# Power_Supply_AC_to_DC.net
KiCad netlist of a schematic drawn in Altium Designer
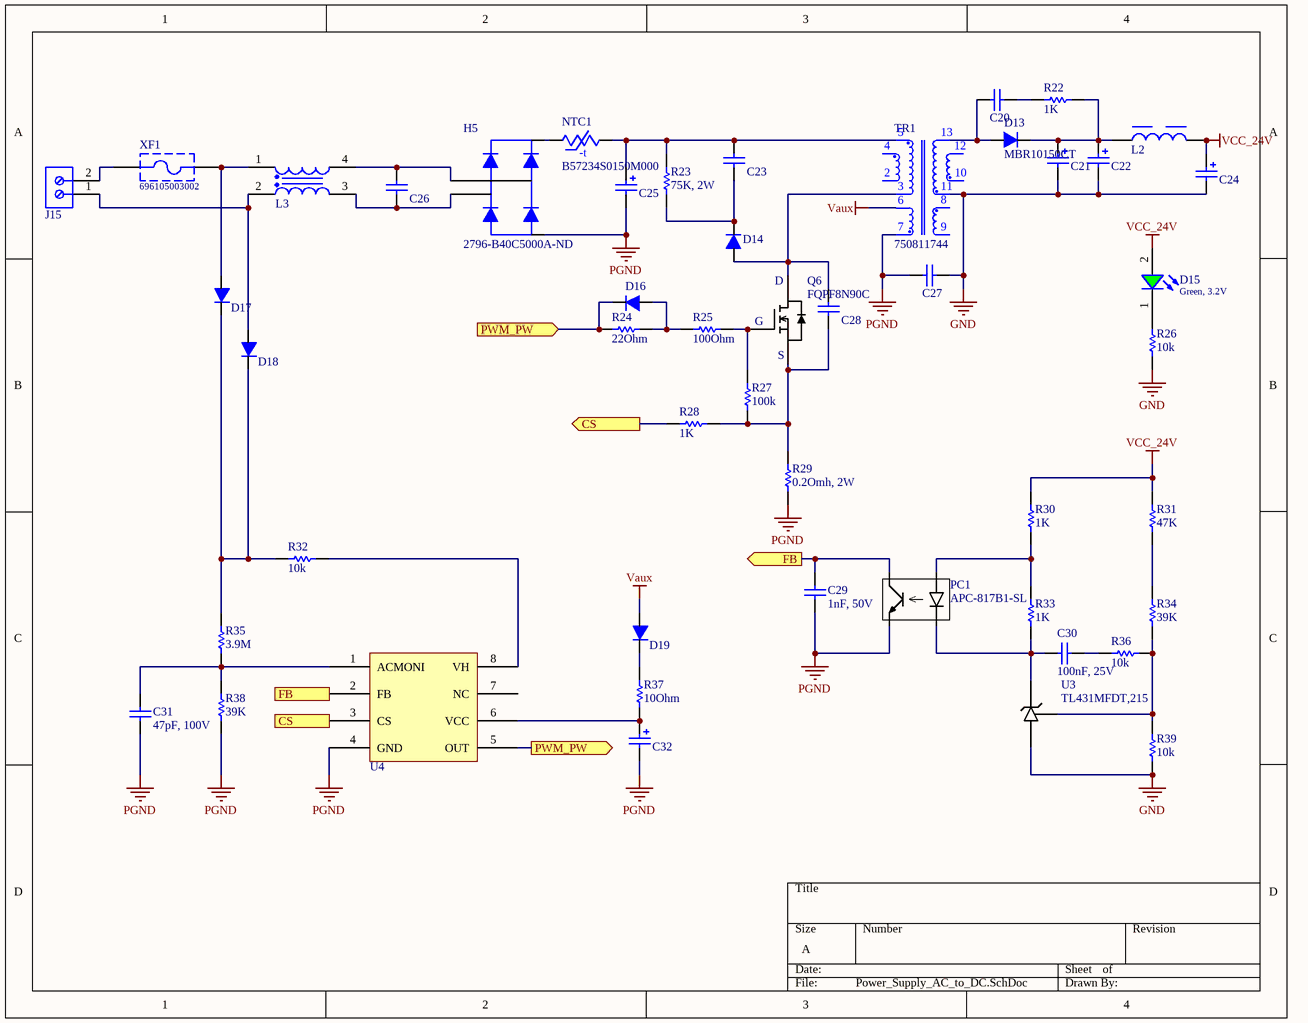
[diagram p0: Power_Supply_AC_to_DC.SchDoc]

(export (version "E")
  (design (tool "Eeschema 10.0.6"))
  (components
    (comp (ref "C20")
      (value "1nF")
      (footprint "WCAP-CSMH_0805_L2W1.25H0.8_Reflow")
      (fields
        (field (name "MANUFACTURER PART NUMBER") "885342207013")
        (field (name "MANUFACTURER") "Wurth Elektronik")
      )
      (libsource (lib "Altium_WCAP-CSMH (rev22c)") (part "885342207013"))
    )
    (comp (ref "C21")
      (value "1200uF")
      (footprint "WCAP-ATG8_D16H31.5")
      (description "WCAP-ATG8 Aluminum Electrolytic Capacitor, Radial THT, D16xH31.5mm, 1200uF, 63V")
      (fields
        (field (name "MANUFACTURER") "Wurth Elektronik")
        (field (name "MANUFACTURER PART NUMBER") "860010780025")
      )
      (libsource (lib "Altium_WCAP-ATG8 (rev22a)") (part "860010780025"))
    )
    (comp (ref "C22")
      (value "1200uF")
      (footprint "WCAP-ATG8_D16H31.5")
      (description "WCAP-ATG8 Aluminum Electrolytic Capacitor, Radial THT, D16xH31.5mm, 1200uF, 63V")
      (fields
        (field (name "MANUFACTURER") "Wurth Elektronik")
        (field (name "MANUFACTURER PART NUMBER") "860010780025")
      )
      (libsource (lib "Altium_WCAP-ATG8 (rev22a)") (part "860010780025"))
    )
    (comp (ref "C23")
      (value "4.7nF")
      (footprint "WCAP-CSMH_1206_L3.2W1.6H1.25")
      (fields
        (field (name "MANUFACTURER PART NUMBER") "885342208008")
        (field (name "MANUFACTURER") "Wurth Elektronik")
      )
      (libsource (lib "Altium_WCAP-CSMH (rev22c)") (part "885342208008"))
    )
    (comp (ref "C24")
      (value "100uF")
      (footprint "WCAP-ATG8_D8H11.5")
      (description "WCAP-ATG8 Aluminum Electrolytic Capacitor, Radial THT, D8xH11.5mm, 100uF, 50V")
      (fields
        (field (name "MANUFACTURER") "Wurth Elektronik")
        (field (name "MANUFACTURER PART NUMBER") "860010674014")
      )
      (libsource (lib "Altium_WCAP-ATG8 (rev22a)") (part "860010674014"))
    )
    (comp (ref "C25")
      (value "220uF")
      (footprint "WCAP-AI3H_D22H50")
      (description "WCAP-AI3H Aluminum Electrolytic Capacitor, Snap-In, D22xH50mm, 220uF, 450V")
      (fields
        (field (name "MANUFACTURER") "Wurth Elektronik")
        (field (name "MANUFACTURER PART NUMBER") "861141483007")
      )
      (libsource (lib "Altium_WCAP-AI3H (rev22a)") (part "861141483007"))
    )
    (comp (ref "C26")
      (value "2.2uF")
      (footprint "WCAP-FTX2_L26W15H25")
      (description "WCAP-FTX2 Film Capacitor, THT, L26W15H25mm, 2.2uF, 275VAC")
      (fields
        (field (name "MANUFACTURER") "Wurth Elektronik")
        (field (name "MANUFACTURER PART NUMBER") "890324026034")
      )
      (libsource (lib "Altium_WCAP-FTX2 (rev22a)") (part "890324026034"))
    )
    (comp (ref "C27")
      (value "2.2nF")
      (footprint "WCAP-CSSA_2211_L5.7W2.8H2.5")
      (description "WCAP-CSSA Multilayer Ceramic Chip Safety Capacitor, 2211, X7R Class II, X1/Y2, 2.2nF, 250VAC")
      (fields
        (field (name "MANUFACTURER") "Wurth Elektronik")
        (field (name "MANUFACTURER PART NUMBER") "8853522130151")
      )
      (libsource (lib "Altium_WCAP-CSSA (rev22a)") (part "8853522130151"))
    )
    (comp (ref "C28")
      (value "22pF")
      (footprint "WCAP-CSMH_1210_L3.2W2.5H0.95")
      (fields
        (field (name "MANUFACTURER PART NUMBER") "885342009002")
        (field (name "MANUFACTURER") "Wurth Elektronik")
      )
      (libsource (lib "Altium_WCAP-CSMH (rev22c)") (part "885342009002"))
    )
    (comp (ref "C29")
      (value "1nF, 50V")
      (footprint "WCAP-CSGP_0805_H=0.8mm_Reflow")
      (description "WCAP-CSGP Multilayer Ceramic Chip Capacitor, General Purpose, size 0805, NP0, 1nF, 50V")
      (fields
        (field (name "MANUFACTURER PART NUMBER") "885012007063")
        (field (name "MANUFACTURER") "Wurth Elektronik")
      )
      (libsource (lib "Altium_WCAP-CSGP (rev20a)") (part "885012007063"))
    )
    (comp (ref "C30")
      (value "100nF, 25V")
      (footprint "WCAP-CSGP_0805_H=0.8mm_Reflow")
      (description "WCAP-CSGP Multilayer Ceramic Chip Capacitor, General Purpose, size 0805, X7R, 100nF, 25V")
      (fields
        (field (name "MANUFACTURER PART NUMBER") "885012207072")
        (field (name "MANUFACTURER") "Wurth Elektronik")
      )
      (libsource (lib "Altium_WCAP-CSGP (rev20a)") (part "885012207072"))
    )
    (comp (ref "C31")
      (value "47pF, 100V")
      (footprint "WCAP-CSGP_0805_H=0.6mm_Reflow")
      (description "WCAP-CSGP Multilayer Ceramic Chip Capacitor, General Purpose, size 0805, NP0, 47pF, 100V")
      (fields
        (field (name "MANUFACTURER PART NUMBER") "885012007080")
        (field (name "MANUFACTURER") "Wurth Elektronik")
      )
      (libsource (lib "Altium_WCAP-CSGP (rev20a)") (part "885012007080"))
    )
    (comp (ref "C32")
      (value "10uF")
      (footprint "WCAP-ATG8_D5H11")
      (description "WCAP-ATG8 Aluminum Electrolytic Capacitor, Radial THT, D5xH11mm, 10uF, 50V")
      (fields
        (field (name "MANUFACTURER") "Wurth Elektronik")
        (field (name "MANUFACTURER PART NUMBER") "860010672009")
      )
      (libsource (lib "Altium_WCAP-ATG8 (rev22a)") (part "860010672009"))
    )
    (comp (ref "D13")
      (value "MBR10150CT")
      (footprint "MBR10150CT")
      (description "DIODE ARRAY SCHOTTKY 150V TO220")
      (fields (field (name "MFR") "SMC Diode Solutions"))
      (libsource (lib "YenDoo") (part "Diode"))
    )
    (comp (ref "D14")
      (value "RS1M-13-F")
      (footprint "SMA")
      (description "DIODE GEN PURP 1KV 1A SMA")
      (fields (field (name "MFR") "Diodes Incorporated"))
      (libsource (lib "YenDoo") (part "Diode"))
    )
    (comp (ref "D15")
      (value "Green, 3.2V")
      (footprint "WL-SMCW_0603_H=0.7mm")
      (description "WL-SMCW SMT Mono-color Chip LED Waterclear, size 0603, Green, 3.2V, 140deg")
      (fields (field (name "PART NUMBER") "150060GS75000") (field (name "PUBLISHER") "Wurth Elektronik"))
      (libsource (lib "Altium_WL-SMCW (rev20a)") (part "150060GS75000"))
    )
    (comp (ref "D16")
      (value "CDBA360-HF")
      (footprint "SMA")
      (description "DIODE SCHOTTKY 60V 3A DO214AC")
      (fields (field (name "MFR") "Comchip Technology"))
      (libsource (lib "YenDoo") (part "Diode"))
    )
    (comp (ref "D17")
      (value "RFU02VSM8STR")
      (footprint "Flat Lead")
      (description "DIODE GP 800V 200MA TUMD2SM")
      (fields (field (name "MFR") "Rohm Semiconductor"))
      (libsource (lib "YenDoo") (part "Diode"))
    )
    (comp (ref "D18")
      (value "RFU02VSM8STR")
      (footprint "Flat Lead")
      (description "DIODE GP 800V 200MA TUMD2SM")
      (fields (field (name "MFR") "Rohm Semiconductor"))
      (libsource (lib "YenDoo") (part "Diode"))
    )
    (comp (ref "D19")
      (value "RS1M-13-F")
      (footprint "SMA")
      (description "DIODE GEN PURP 1KV 1A SMA")
      (fields (field (name "MFR") "Diodes Incorporated"))
      (libsource (lib "YenDoo") (part "Diode"))
    )
    (comp (ref "H5")
      (value "2796-B40C5000A-ND")
      (footprint "GBJ-4")
      (description "Bridge Rectifier Single Phase Standard 80 V Through Hole 4-SIP")
      (libsource (lib "YenDoo") (part "H Bridge"))
    )
    (comp (ref "J15")
      (value "691137710002")
      (footprint "691137710002")
      (description "WR-TBL Series 1377 Horizontal Entry, Through Hole, pitch 5mm, 2p")
      (fields (field (name "MANUFACTURER") "Wurth Elektronik"))
      (libsource (lib "Altium_WR-TBL (rev22a)") (part "691137710002"))
    )
    (comp (ref "L2")
      (value "10µH, 7A")
      (footprint "WE-LHMI_1040")
      (description "WE-LHMI SMT Power Inductor, size 1040, 10µH, 7A, 30mΩ")
      (fields
        (field (name "MANUFACTURER PART NUMBER") "74437368100")
        (field (name "MANUFACTURER") "Wurth Elektronik")
      )
      (libsource (lib "WE-LHMI (rev22a)") (part "74437368100"))
    )
    (comp (ref "L3")
      (value "13mH")
      (footprint "WE-FC_UT20V")
      (description "WE-FC THT Common Mode Power Line Choke, UT20V, 13mH, 0.8A, 0.708Ω")
      (fields
        (field (name "MANUFACTURER PART NUMBER") "7448640415")
        (field (name "MANUFACTURER") "Wurth Elektronik")
      )
      (libsource (lib "WE-FC (rev22a)") (part "7448640415"))
    )
    (comp (ref "NTC1")
      (value "B57234S0150M000")
      (footprint "NTC")
      (description "THERMISTOR NTC 15OHM 3000K")
      (fields (field (name "MFR") "EPCOS - TDK Electronics") (field (name "TOLERANCE") "±20%"))
      (libsource (lib "YenDoo") (part "NTC"))
    )
    (comp (ref "PC1")
      (value "APC-817B1-SL")
      (footprint "APC-817B1-SL")
      (description "DIP4, DC INPUT, PHOTO TRANSISTOR")
      (fields (field (name "MFR") "American Bright Optoelectronics Corporation"))
      (libsource (lib "YenDoo") (part "Opto Isolator"))
    )
    (comp (ref "Q6")
      (value "FQPF8N90C")
      (footprint "FQPF8N90C")
      (description "MOSFET N-CH 900V 6.3A TO220F")
      (fields (field (name "MFR") "onsemi"))
      (libsource (lib "YenDoo") (part "Mosfet"))
    )
    (comp (ref "R22")
      (value "1K")
      (footprint "RES-SM-2512")
      (description "RES 10 OHM 0.5% 1W 2512")
      (fields (field (name "MFR") "KOA Speer Electronics, Inc.") (field (name "TOLERANCE") "±0.5%"))
      (libsource (lib "PIF_Library") (part "RESISTOR SMD"))
    )
    (comp (ref "R23")
      (value "75K, 2W")
      (footprint "RES-SM-2512")
      (description "RES SMD 75K OHM 1% 2W 2512")
      (fields (field (name "MFR") "TE Connectivity Passive Product") (field (name "TOLERANCE") "±1%"))
      (libsource (lib "PIF_Library") (part "RESISTOR SMD"))
    )
    (comp (ref "R24")
      (value "22Ohm")
      (footprint "RES-SM-0805")
      (description "RES 22 OHM 1% 1/4W 0805")
      (fields (field (name "MFR") "KOA Speer Electronics, Inc.") (field (name "TOLERANCE") "±1%"))
      (libsource (lib "PIF_Library") (part "RESISTOR SMD"))
    )
    (comp (ref "R25")
      (value "100Ohm")
      (footprint "RES-SM-0805")
      (description "RES 100 OHM 5% 1/4W 0805")
      (fields (field (name "MFR") "KOA Speer Electronics, Inc.") (field (name "TOLERANCE") "±5%"))
      (libsource (lib "PIF_Library") (part "RESISTOR SMD"))
    )
    (comp (ref "R26")
      (value "10k")
      (footprint "RES-SM-0805")
      (description "RES 10K OHM 1% 1/4W 0805")
      (fields (field (name "MFR") "KOA Speer Electronics, Inc.") (field (name "TOLERANCE") "±1%"))
      (libsource (lib "PIF_Library") (part "RESISTOR SMD"))
    )
    (comp (ref "R27")
      (value "100k")
      (footprint "RES-SM-0805")
      (description "RES 100K OHM 1% 1/4W 0805")
      (fields (field (name "MFR") "KOA Speer Electronics, Inc.") (field (name "TOLERANCE") "±1%"))
      (libsource (lib "PIF_Library") (part "RESISTOR SMD"))
    )
    (comp (ref "R28")
      (value "1K")
      (footprint "RES-SM-0805")
      (description "RES 1K OHM 5% 1/4W 0805")
      (fields (field (name "MFR") "KOA Speer Electronics, Inc.") (field (name "TOLERANCE") "±5%"))
      (libsource (lib "PIF_Library") (part "RESISTOR SMD"))
    )
    (comp (ref "R29")
      (value "0.2Omh, 2W")
      (footprint "RES-SM-2010")
      (description "RES 0.2 OHM 2.0 W 1% 2010 SMD")
      (fields (field (name "MFR") "Vishay Dale") (field (name "TOLERANCE") "±1%"))
      (libsource (lib "PIF_Library") (part "RESISTOR SMD"))
    )
    (comp (ref "R30")
      (value "1K")
      (footprint "RES-SM-0805")
      (description "RES 1K OHM 5% 1/4W 0805")
      (fields (field (name "MFR") "KOA Speer Electronics, Inc.") (field (name "TOLERANCE") "±5%"))
      (libsource (lib "PIF_Library") (part "RESISTOR SMD"))
    )
    (comp (ref "R31")
      (value "47K")
      (footprint "RES-SM-0805")
      (description "RES 47K OHM 5% 1/4W 0805")
      (fields (field (name "MFR") "KOA Speer Electronics, Inc.") (field (name "TOLERANCE") "±5%"))
      (libsource (lib "PIF_Library") (part "RESISTOR SMD"))
    )
    (comp (ref "R32")
      (value "10k")
      (footprint "RES-SM-0805")
      (description "RES 10K OHM 1% 1/4W 0805")
      (fields (field (name "MFR") "KOA Speer Electronics, Inc.") (field (name "TOLERANCE") "±1%"))
      (libsource (lib "PIF_Library") (part "RESISTOR SMD"))
    )
    (comp (ref "R33")
      (value "1K")
      (footprint "RES-SM-0805")
      (description "RES 1K OHM 5% 1/4W 0805")
      (fields (field (name "MFR") "KOA Speer Electronics, Inc.") (field (name "TOLERANCE") "±5%"))
      (libsource (lib "PIF_Library") (part "RESISTOR SMD"))
    )
    (comp (ref "R34")
      (value "39K")
      (footprint "RES-SM-0805")
      (description "RES 39K OHM 5% 1/4W 0805")
      (fields (field (name "MFR") "KOA Speer Electronics, Inc.") (field (name "TOLERANCE") "±5%"))
      (libsource (lib "PIF_Library") (part "RESISTOR SMD"))
    )
    (comp (ref "R35")
      (value "3.9M")
      (footprint "RES-SM-0805")
      (description "RES 3.9M OHM 5% 1/4W 0805")
      (fields (field (name "MFR") "KOA Speer Electronics, Inc.") (field (name "TOLERANCE") "±5%"))
      (libsource (lib "PIF_Library") (part "RESISTOR SMD"))
    )
    (comp (ref "R36")
      (value "10k")
      (footprint "RES-SM-0805")
      (description "RES 10K OHM 1% 1/4W 0805")
      (fields (field (name "MFR") "KOA Speer Electronics, Inc.") (field (name "TOLERANCE") "±1%"))
      (libsource (lib "PIF_Library") (part "RESISTOR SMD"))
    )
    (comp (ref "R37")
      (value "10Ohm")
      (footprint "RES-SM-0805")
      (description "RES 10 OHM 1% 1/4W 0805")
      (fields (field (name "MFR") "KOA Speer Electronics, Inc.") (field (name "TOLERANCE") "±1%"))
      (libsource (lib "PIF_Library") (part "RESISTOR SMD"))
    )
    (comp (ref "R38")
      (value "39K")
      (footprint "RES-SM-0805")
      (description "RES 39K OHM 5% 1/4W 0805")
      (fields (field (name "MFR") "KOA Speer Electronics, Inc.") (field (name "TOLERANCE") "±5%"))
      (libsource (lib "PIF_Library") (part "RESISTOR SMD"))
    )
    (comp (ref "R39")
      (value "10k")
      (footprint "RES-SM-0805")
      (description "RES 10K OHM 1% 1/4W 0805")
      (fields (field (name "MFR") "KOA Speer Electronics, Inc.") (field (name "TOLERANCE") "±1%"))
      (libsource (lib "PIF_Library") (part "RESISTOR SMD"))
    )
    (comp (ref "TR1")
      (value "750811744")
      (footprint "750811744")
      (description "Flyback Converters For For DC/DC Converters SMPS Transformer 4000Vrms Isolation 80kHz Through Hole")
      (fields (field (name "MFR") "Würth Elektronik"))
      (libsource (lib "YenDoo") (part "750811744"))
    )
    (comp (ref "U3")
      (value "TL431MFDT,215")
      (footprint "TO-236AB")
      (description "IC VREF SHUNT ADJ 2% TO236AB")
      (fields (field (name "MFR") "Nexperia USA Inc.") (field (name "TOLERANCE") "±2%"))
      (libsource (lib "YenDoo") (part "IC Shunt"))
    )
    (comp (ref "U4")
      (value "BM1P061FJ-E2")
      (footprint "SOP-J8")
      (description "IC OFFLINE SWITCH FLYBACK 8SOPJ")
      (fields (field (name "MFR") "Rohm Semiconductor"))
      (libsource (lib "YenDoo") (part "IC PWM"))
    )
    (comp (ref "XF1")
      (value "696105003002")
      (footprint "696105003002")
      (description "WR-FSH Fuseholder THT Blocks PCB Clip Cover")
      (fields (field (name "MANUFACTURER") "Wurth Elektronik"))
      (libsource (lib "Altium_WR-FSH (rev21a)") (part "696105003002"))
    )
  )
  (nets
    (net (code "1") (name "/CS") (class "Default")
      (node (ref "R28") (pin "2") (pinfunction "2_2") (pintype "passive"))
      (node (ref "U4") (pin "3") (pinfunction "CS_3") (pintype "passive"))
    )
    (net (code "2") (name "/FB") (class "Default")
      (node (ref "C29") (pin "2") (pinfunction "2_2") (pintype "passive"))
      (node (ref "PC1") (pin "4") (pinfunction "4_4") (pintype "passive"))
      (node (ref "U4") (pin "2") (pinfunction "FB_2") (pintype "passive"))
    )
    (net (code "3") (name "/PWM_PW") (class "Default")
      (node (ref "D16") (pin "2") (pinfunction "K_2") (pintype "passive"))
      (node (ref "R24") (pin "1") (pinfunction "1_1") (pintype "passive"))
      (node (ref "U4") (pin "5") (pinfunction "OUT_5") (pintype "passive"))
    )
    (net (code "4") (name "GND") (class "Default")
      (node (ref "C21") (pin "2") (pinfunction "N_2") (pintype "passive"))
      (node (ref "C22") (pin "2") (pinfunction "N_2") (pintype "passive"))
      (node (ref "C24") (pin "2") (pinfunction "N_2") (pintype "passive"))
      (node (ref "C27") (pin "1") (pinfunction "1_1") (pintype "passive"))
      (node (ref "R26") (pin "2") (pinfunction "2_2") (pintype "passive"))
      (node (ref "R39") (pin "2") (pinfunction "2_2") (pintype "passive"))
      (node (ref "TR1") (pin "11") (pinfunction "11_11") (pintype "passive"))
      (node (ref "U3") (pin "3") (pinfunction "3_3") (pintype "passive"))
    )
    (net (code "5") (name "Net-(C20-Pad2)") (class "Default")
      (node (ref "C20") (pin "2") (pinfunction "2_2") (pintype "passive"))
      (node (ref "R22") (pin "1") (pinfunction "1_1") (pintype "passive"))
    )
    (net (code "6") (name "Net-(C21-P)") (class "Default")
      (node (ref "C21") (pin "1") (pinfunction "P_1") (pintype "passive"))
      (node (ref "C22") (pin "1") (pinfunction "P_1") (pintype "passive"))
      (node (ref "D13") (pin "2") (pinfunction "K_2") (pintype "passive"))
      (node (ref "L2") (pin "1") (pinfunction "1_1") (pintype "passive"))
      (node (ref "R22") (pin "2") (pinfunction "2_2") (pintype "passive"))
    )
    (net (code "7") (name "Net-(C25-P)") (class "Default")
      (node (ref "C23") (pin "2") (pinfunction "2_2") (pintype "passive"))
      (node (ref "C25") (pin "1") (pinfunction "P_1") (pintype "passive"))
      (node (ref "NTC1") (pin "2") (pinfunction "2_2") (pintype "passive"))
      (node (ref "R23") (pin "2") (pinfunction "2_2") (pintype "passive"))
      (node (ref "TR1") (pin "5") (pinfunction "5_5") (pintype "passive"))
    )
    (net (code "8") (name "Net-(C26-Pad1)") (class "Default")
      (node (ref "C26") (pin "1") (pinfunction "1_1") (pintype "passive"))
      (node (ref "H5") (pin "3") (pinfunction "~_3") (pintype "passive"))
      (node (ref "L3") (pin "3") (pinfunction "3_3") (pintype "passive"))
    )
    (net (code "9") (name "Net-(C26-Pad2)") (class "Default")
      (node (ref "C26") (pin "2") (pinfunction "2_2") (pintype "passive"))
      (node (ref "H5") (pin "2") (pinfunction "~_2") (pintype "passive"))
      (node (ref "L3") (pin "4") (pinfunction "4_4") (pintype "passive"))
    )
    (net (code "10") (name "Net-(C30-Pad1)") (class "Default")
      (node (ref "C30") (pin "1") (pinfunction "1_1") (pintype "passive"))
      (node (ref "PC1") (pin "2") (pinfunction "2_2") (pintype "passive"))
      (node (ref "R33") (pin "2") (pinfunction "2_2") (pintype "passive"))
      (node (ref "U3") (pin "1") (pinfunction "1_1") (pintype "passive"))
    )
    (net (code "11") (name "Net-(C30-Pad2)") (class "Default")
      (node (ref "C30") (pin "2") (pinfunction "2_2") (pintype "passive"))
      (node (ref "R36") (pin "1") (pinfunction "1_1") (pintype "passive"))
    )
    (net (code "12") (name "Net-(C32-P)") (class "Default")
      (node (ref "C32") (pin "1") (pinfunction "P_1") (pintype "passive"))
      (node (ref "R37") (pin "1") (pinfunction "1_1") (pintype "passive"))
      (node (ref "U4") (pin "6") (pinfunction "VCC_6") (pintype "passive"))
    )
    (net (code "13") (name "Net-(D13-A)") (class "Default")
      (node (ref "C20") (pin "1") (pinfunction "1_1") (pintype "passive"))
      (node (ref "D13") (pin "1") (pinfunction "A_1") (pintype "passive"))
      (node (ref "TR1") (pin "13") (pinfunction "13_13") (pintype "passive"))
    )
    (net (code "14") (name "Net-(D14-A)") (class "Default")
      (node (ref "C28") (pin "2") (pinfunction "2_2") (pintype "passive"))
      (node (ref "D14") (pin "1") (pinfunction "A_1") (pintype "passive"))
      (node (ref "Q6") (pin "2") (pinfunction "D_2") (pintype "passive"))
      (node (ref "TR1") (pin "3") (pinfunction "3_3") (pintype "passive"))
    )
    (net (code "15") (name "Net-(D14-K)") (class "Default")
      (node (ref "C23") (pin "1") (pinfunction "1_1") (pintype "passive"))
      (node (ref "D14") (pin "2") (pinfunction "K_2") (pintype "passive"))
      (node (ref "R23") (pin "1") (pinfunction "1_1") (pintype "passive"))
    )
    (net (code "16") (name "Net-(D15-K)") (class "Default")
      (node (ref "D15") (pin "1") (pinfunction "K_1") (pintype "passive"))
      (node (ref "R26") (pin "1") (pinfunction "1_1") (pintype "passive"))
    )
    (net (code "17") (name "Net-(D16-A)") (class "Default")
      (node (ref "D16") (pin "1") (pinfunction "A_1") (pintype "passive"))
      (node (ref "R24") (pin "2") (pinfunction "2_2") (pintype "passive"))
      (node (ref "R25") (pin "1") (pinfunction "1_1") (pintype "passive"))
    )
    (net (code "18") (name "Net-(D17-A)") (class "Default")
      (node (ref "D17") (pin "1") (pinfunction "A_1") (pintype "passive"))
      (node (ref "L3") (pin "1") (pinfunction "1_1") (pintype "passive"))
      (node (ref "XF1") (pin "2") (pinfunction "2_2") (pintype "passive"))
    )
    (net (code "19") (name "Net-(D17-K)") (class "Default")
      (node (ref "D17") (pin "2") (pinfunction "K_2") (pintype "passive"))
      (node (ref "D18") (pin "2") (pinfunction "K_2") (pintype "passive"))
      (node (ref "R32") (pin "2") (pinfunction "2_2") (pintype "passive"))
      (node (ref "R35") (pin "2") (pinfunction "2_2") (pintype "passive"))
    )
    (net (code "20") (name "Net-(D18-A)") (class "Default")
      (node (ref "D18") (pin "1") (pinfunction "A_1") (pintype "passive"))
      (node (ref "J15") (pin "1") (pinfunction "1_1") (pintype "passive"))
      (node (ref "L3") (pin "2") (pinfunction "2_2") (pintype "passive"))
    )
    (net (code "21") (name "Net-(D19-K)") (class "Default")
      (node (ref "D19") (pin "2") (pinfunction "K_2") (pintype "passive"))
      (node (ref "R37") (pin "2") (pinfunction "2_2") (pintype "passive"))
    )
    (net (code "22") (name "Net-(H5-+)") (class "Default")
      (node (ref "H5") (pin "1") (pinfunction "+_1") (pintype "passive"))
      (node (ref "NTC1") (pin "1") (pinfunction "1_1") (pintype "passive"))
    )
    (net (code "23") (name "Net-(J15-Pad2)") (class "Default")
      (node (ref "J15") (pin "2") (pinfunction "2_2") (pintype "passive"))
      (node (ref "XF1") (pin "1") (pinfunction "1_1") (pintype "passive"))
    )
    (net (code "24") (name "Net-(PC1-Pad1)") (class "Default")
      (node (ref "PC1") (pin "1") (pinfunction "1_1") (pintype "passive"))
      (node (ref "R30") (pin "2") (pinfunction "2_2") (pintype "passive"))
      (node (ref "R33") (pin "1") (pinfunction "1_1") (pintype "passive"))
    )
    (net (code "25") (name "Net-(Q6-G)") (class "Default")
      (node (ref "Q6") (pin "1") (pinfunction "G_1") (pintype "passive"))
      (node (ref "R25") (pin "2") (pinfunction "2_2") (pintype "passive"))
      (node (ref "R27") (pin "2") (pinfunction "2_2") (pintype "passive"))
    )
    (net (code "26") (name "Net-(Q6-S)") (class "Default")
      (node (ref "C28") (pin "1") (pinfunction "1_1") (pintype "passive"))
      (node (ref "Q6") (pin "3") (pinfunction "S_3") (pintype "passive"))
      (node (ref "R27") (pin "1") (pinfunction "1_1") (pintype "passive"))
      (node (ref "R28") (pin "1") (pinfunction "1_1") (pintype "passive"))
      (node (ref "R29") (pin "2") (pinfunction "2_2") (pintype "passive"))
    )
    (net (code "27") (name "Net-(R31-Pad1)") (class "Default")
      (node (ref "R31") (pin "1") (pinfunction "1_1") (pintype "passive"))
      (node (ref "R34") (pin "2") (pinfunction "2_2") (pintype "passive"))
    )
    (net (code "28") (name "Net-(R34-Pad1)") (class "Default")
      (node (ref "R34") (pin "1") (pinfunction "1_1") (pintype "passive"))
      (node (ref "R36") (pin "2") (pinfunction "2_2") (pintype "passive"))
      (node (ref "R39") (pin "1") (pinfunction "1_1") (pintype "passive"))
      (node (ref "U3") (pin "2") (pinfunction "2_2") (pintype "passive"))
    )
    (net (code "29") (name "Net-(U4-ACMONI)") (class "Default")
      (node (ref "C31") (pin "2") (pinfunction "2_2") (pintype "passive"))
      (node (ref "R35") (pin "1") (pinfunction "1_1") (pintype "passive"))
      (node (ref "R38") (pin "2") (pinfunction "2_2") (pintype "passive"))
      (node (ref "U4") (pin "1") (pinfunction "ACMONI_1") (pintype "passive"))
    )
    (net (code "30") (name "Net-(U4-VH)") (class "Default")
      (node (ref "R32") (pin "1") (pinfunction "1_1") (pintype "passive"))
      (node (ref "U4") (pin "8") (pinfunction "VH_8") (pintype "passive"))
    )
    (net (code "31") (name "PGND") (class "Default")
      (node (ref "C25") (pin "2") (pinfunction "N_2") (pintype "passive"))
      (node (ref "C27") (pin "2") (pinfunction "2_2") (pintype "passive"))
      (node (ref "C29") (pin "1") (pinfunction "1_1") (pintype "passive"))
      (node (ref "C31") (pin "1") (pinfunction "1_1") (pintype "passive"))
      (node (ref "C32") (pin "2") (pinfunction "N_2") (pintype "passive"))
      (node (ref "H5") (pin "4") (pinfunction "-_4") (pintype "passive"))
      (node (ref "PC1") (pin "3") (pinfunction "3_3") (pintype "passive"))
      (node (ref "R29") (pin "1") (pinfunction "1_1") (pintype "passive"))
      (node (ref "R38") (pin "1") (pinfunction "1_1") (pintype "passive"))
      (node (ref "TR1") (pin "7") (pinfunction "7_7") (pintype "passive"))
      (node (ref "U4") (pin "4") (pinfunction "GND_4") (pintype "passive"))
    )
    (net (code "32") (name "VCC_24V") (class "Default")
      (node (ref "C24") (pin "1") (pinfunction "P_1") (pintype "passive"))
      (node (ref "D15") (pin "2") (pinfunction "A_2") (pintype "passive"))
      (node (ref "L2") (pin "2") (pinfunction "2_2") (pintype "passive"))
      (node (ref "R30") (pin "1") (pinfunction "1_1") (pintype "passive"))
      (node (ref "R31") (pin "2") (pinfunction "2_2") (pintype "passive"))
    )
    (net (code "33") (name "Vaux") (class "Default")
      (node (ref "D19") (pin "1") (pinfunction "A_1") (pintype "passive"))
      (node (ref "TR1") (pin "6") (pinfunction "6_6") (pintype "passive"))
    )
    (net (code "34") (name "unconnected-(TR1-Pad2)") (class "Default")
      (node (ref "TR1") (pin "2") (pinfunction "2_2") (pintype "passive"))
    )
    (net (code "35") (name "unconnected-(TR1-Pad4)") (class "Default")
      (node (ref "TR1") (pin "4") (pinfunction "4_4") (pintype "passive"))
    )
    (net (code "36") (name "unconnected-(TR1-Pad8)") (class "Default")
      (node (ref "TR1") (pin "8") (pinfunction "8_8") (pintype "passive"))
    )
    (net (code "37") (name "unconnected-(TR1-Pad9)") (class "Default")
      (node (ref "TR1") (pin "9") (pinfunction "9_9") (pintype "passive"))
    )
    (net (code "38") (name "unconnected-(TR1-Pad10)") (class "Default")
      (node (ref "TR1") (pin "10") (pinfunction "10_10") (pintype "passive"))
    )
    (net (code "39") (name "unconnected-(TR1-Pad12)") (class "Default")
      (node (ref "TR1") (pin "12") (pinfunction "12_12") (pintype "passive"))
    )
    (net (code "40") (name "unconnected-(U4-NC-Pad7)") (class "Default")
      (node (ref "U4") (pin "7") (pinfunction "NC_7") (pintype "passive"))
    )
  )
)
